# battery_charger.net
KiCad netlist of a schematic drawn in Altium Designer
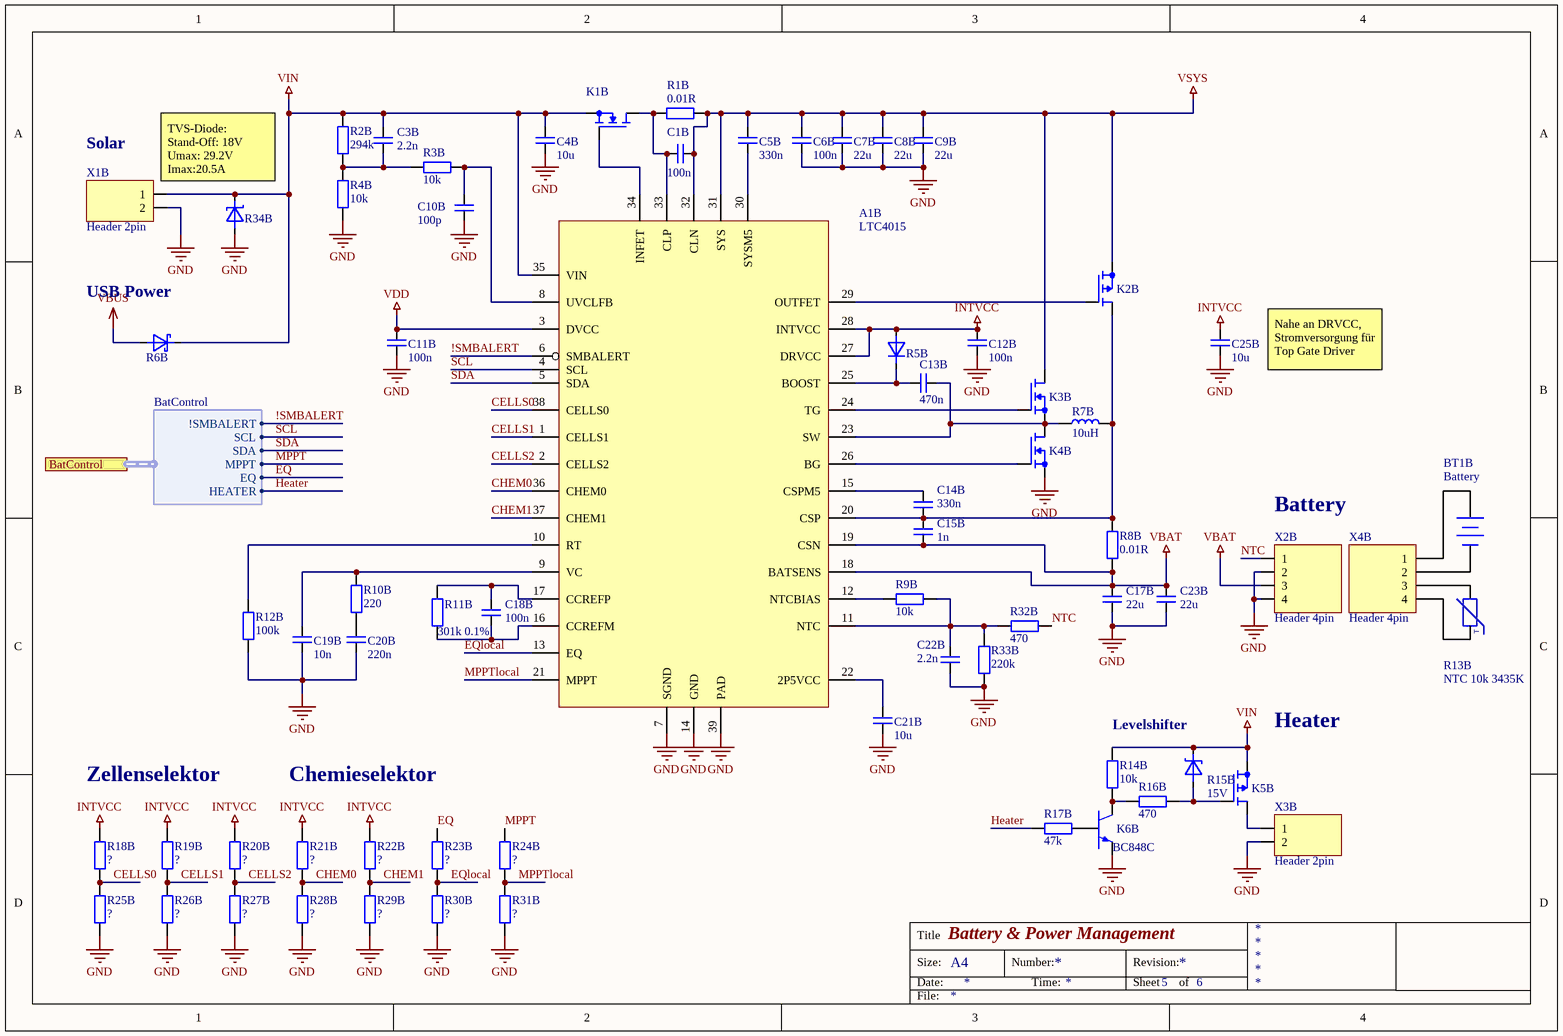
[diagram p0: battery_charger.SchDoc]

(export (version "E")
  (design (tool "Eeschema 10.0.6"))
  (components
    (comp (ref "A1B")
      (value "LTC4015")
      (footprint "QFN38")
      (description "Multichemistry Buck Battery Charger Controller with Digital Telemetry System")
      (libsource (lib "IC") (part "LTC4015"))
    )
    (comp (ref "BT1B")
      (value "Battery")
      (description "Multicell Battery")
      (fields (field (name "PUBLISHER") "Altium Limited"))
      (libsource (lib "Miscellaneous Devices") (part "Battery"))
    )
    (comp (ref "C1B") (value "100n") (footprint "0805") (libsource (lib "Passive") (part "Kondensator")))
    (comp (ref "C3B") (value "2.2n") (footprint "0805") (libsource (lib "Passive") (part "Kondensator")))
    (comp (ref "C4B") (value "10u") (footprint "1812") (libsource (lib "Passive") (part "Kondensator")))
    (comp (ref "C5B") (value "330n") (footprint "0805") (libsource (lib "Passive") (part "Kondensator")))
    (comp (ref "C6B") (value "100n") (footprint "0805") (libsource (lib "Passive") (part "Kondensator")))
    (comp (ref "C7B") (value "22u") (footprint "1812") (libsource (lib "Passive") (part "Kondensator")))
    (comp (ref "C8B") (value "22u") (footprint "1812") (libsource (lib "Passive") (part "Kondensator")))
    (comp (ref "C9B") (value "22u") (footprint "1812") (libsource (lib "Passive") (part "Kondensator")))
    (comp (ref "C10B") (value "100p") (footprint "0805") (libsource (lib "Passive") (part "Kondensator")))
    (comp (ref "C11B") (value "100n") (footprint "0805") (libsource (lib "Passive") (part "Kondensator")))
    (comp (ref "C12B") (value "100n") (footprint "0805") (libsource (lib "Passive") (part "Kondensator")))
    (comp (ref "C13B") (value "470n") (footprint "0805") (libsource (lib "Passive") (part "Kondensator")))
    (comp (ref "C14B") (value "330n") (footprint "0805") (libsource (lib "Passive") (part "Kondensator")))
    (comp (ref "C15B") (value "1n") (footprint "0805") (libsource (lib "Passive") (part "Kondensator")))
    (comp (ref "C17B") (value "22u") (footprint "1210") (libsource (lib "Passive") (part "Kondensator")))
    (comp (ref "C18B") (value "100n") (footprint "0805") (libsource (lib "Passive") (part "Kondensator")))
    (comp (ref "C19B") (value "10n") (footprint "0805") (libsource (lib "Passive") (part "Kondensator")))
    (comp (ref "C20B") (value "220n") (footprint "0805") (libsource (lib "Passive") (part "Kondensator")))
    (comp (ref "C21B") (value "10u") (footprint "0805") (libsource (lib "Passive") (part "Kondensator")))
    (comp (ref "C22B") (value "2.2n") (footprint "0805") (libsource (lib "Passive") (part "Kondensator")))
    (comp (ref "C23B") (value "22u") (footprint "1210") (libsource (lib "Passive") (part "Kondensator")))
    (comp (ref "C25B") (value "10u") (footprint "0805") (libsource (lib "Passive") (part "Kondensator")))
    (comp (ref "K1B")
      (value "FDMC8327L")
      (footprint "Power33")
      (libsource (lib "Discrete_Semiconductors") (part "MOSFET N-channel enh"))
    )
    (comp (ref "K2B")
      (value "SI7611DN")
      (footprint "Power33")
      (libsource (lib "Discrete_Semiconductors") (part "MOSFET P-channel enh"))
    )
    (comp (ref "K3B")
      (value "FDMC8327L")
      (footprint "Power33")
      (libsource (lib "Discrete_Semiconductors") (part "MOSFET N-channel enh"))
    )
    (comp (ref "K4B")
      (value "FDMC8327L")
      (footprint "Power33")
      (libsource (lib "Discrete_Semiconductors") (part "MOSFET N-channel enh"))
    )
    (comp (ref "K5B")
      (value "pmos FDC658")
      (footprint "SuperSOT-6")
      (libsource (lib "Discrete_Semiconductors") (part "MOSFET P-channel enh"))
    )
    (comp (ref "K6B")
      (value "BC848C")
      (footprint "SOT23-3")
      (libsource (lib "Discrete_Semiconductors") (part "Transistor NPN"))
    )
    (comp (ref "R1B") (value "0.01R") (footprint "2512") (libsource (lib "Passive") (part "Widerstand")))
    (comp (ref "R2B") (value "294k") (footprint "0805") (libsource (lib "Passive") (part "Widerstand")))
    (comp (ref "R3B") (value "10k") (footprint "0805") (libsource (lib "Passive") (part "Widerstand")))
    (comp (ref "R4B") (value "10k") (footprint "0805") (libsource (lib "Passive") (part "Widerstand")))
    (comp (ref "R5B")
      (value "1N4148W")
      (footprint "SOD123F")
      (libsource (lib "Discrete_Semiconductors") (part "Diode"))
    )
    (comp (ref "R6B")
      (value "Diode shottky")
      (footprint "PowerDI123")
      (libsource (lib "Discrete_Semiconductors") (part "Diode shottky"))
    )
    (comp (ref "R7B")
      (value "10uH")
      (footprint "INDP_13.2_12.9X3.5M")
      (libsource (lib "Passive") (part "Induktivität"))
    )
    (comp (ref "R8B") (value "0.01R") (footprint "2512") (libsource (lib "Passive") (part "Widerstand")))
    (comp (ref "R9B") (value "10k") (footprint "0805") (libsource (lib "Passive") (part "Widerstand")))
    (comp (ref "R10B") (value "220") (footprint "0805") (libsource (lib "Passive") (part "Widerstand")))
    (comp (ref "R11B") (value "301k 0.1%") (footprint "0805") (libsource (lib "Passive") (part "Widerstand")))
    (comp (ref "R12B") (value "100k") (footprint "0805") (libsource (lib "Passive") (part "Widerstand")))
    (comp (ref "R13B") (value "NTC 10k 3435K") (libsource (lib "Passive") (part "PTC")))
    (comp (ref "R14B") (value "10k") (footprint "0805") (libsource (lib "Passive") (part "Widerstand")))
    (comp (ref "R15B")
      (value "15V")
      (footprint "SOD523")
      (libsource (lib "Discrete_Semiconductors") (part "Diode zener"))
    )
    (comp (ref "R16B") (value "470") (footprint "0805") (libsource (lib "Passive") (part "Widerstand")))
    (comp (ref "R17B") (value "47k") (footprint "0805") (libsource (lib "Passive") (part "Widerstand")))
    (comp (ref "R18B") (value "?") (footprint "0805") (libsource (lib "Passive") (part "Widerstand")))
    (comp (ref "R19B") (value "?") (footprint "0805") (libsource (lib "Passive") (part "Widerstand")))
    (comp (ref "R20B") (value "?") (footprint "0805") (libsource (lib "Passive") (part "Widerstand")))
    (comp (ref "R21B") (value "?") (footprint "0805") (libsource (lib "Passive") (part "Widerstand")))
    (comp (ref "R22B") (value "?") (footprint "0805") (libsource (lib "Passive") (part "Widerstand")))
    (comp (ref "R23B") (value "?") (footprint "0805") (libsource (lib "Passive") (part "Widerstand")))
    (comp (ref "R24B") (value "?") (footprint "0805") (libsource (lib "Passive") (part "Widerstand")))
    (comp (ref "R25B") (value "?") (footprint "0805") (libsource (lib "Passive") (part "Widerstand")))
    (comp (ref "R26B") (value "?") (footprint "0805") (libsource (lib "Passive") (part "Widerstand")))
    (comp (ref "R27B") (value "?") (footprint "0805") (libsource (lib "Passive") (part "Widerstand")))
    (comp (ref "R28B") (value "?") (footprint "0805") (libsource (lib "Passive") (part "Widerstand")))
    (comp (ref "R29B") (value "?") (footprint "0805") (libsource (lib "Passive") (part "Widerstand")))
    (comp (ref "R30B") (value "?") (footprint "0805") (libsource (lib "Passive") (part "Widerstand")))
    (comp (ref "R31B") (value "?") (footprint "0805") (libsource (lib "Passive") (part "Widerstand")))
    (comp (ref "R32B") (value "470") (footprint "0805") (libsource (lib "Passive") (part "Widerstand")))
    (comp (ref "R33B") (value "220k") (footprint "0805") (libsource (lib "Passive") (part "Widerstand")))
    (comp (ref "R34B")
      (value "TVS 29.2Vmax")
      (footprint "DO 214AA")
      (description "unipolar transient voltage suppression diode")
      (libsource (lib "Discrete_Semiconductors") (part "Diode TVS unipolar"))
    )
    (comp (ref "X1B")
      (value "Header 2pin")
      (footprint "PHOENIX_1729128")
      (libsource (lib "Connectors") (part "Header 2pin"))
    )
    (comp (ref "X2B")
      (value "Header 4pin")
      (footprint "Phoenix, 5mm pitch, 4pin")
      (libsource (lib "Connectors") (part "Header 4pin"))
    )
    (comp (ref "X3B")
      (value "Header 2pin")
      (footprint "PHOENIX_1729128")
      (libsource (lib "") (part "Header 2pin_1"))
    )
    (comp (ref "X4B") (value "Header 4pin") (libsource (lib "") (part "Header 4pin_1")))
  )
  (nets
    (net (code "2") (name "/!SMBALERT") (class "Default")
      (node (ref "A1B") (pin "6") (pinfunction "SMBALERT_6") (pintype "passive"))
    )
    (net (code "3") (name "/CELLS0") (class "Default")
      (node (ref "A1B") (pin "38") (pinfunction "CELLS0_38") (pintype "passive"))
      (node (ref "R18B") (pin "2") (pinfunction "2_2") (pintype "passive"))
      (node (ref "R25B") (pin "1") (pinfunction "1_1") (pintype "passive"))
    )
    (net (code "4") (name "/CELLS1") (class "Default")
      (node (ref "A1B") (pin "1") (pinfunction "CELLS1_1") (pintype "passive"))
      (node (ref "R19B") (pin "2") (pinfunction "2_2") (pintype "passive"))
      (node (ref "R26B") (pin "1") (pinfunction "1_1") (pintype "passive"))
    )
    (net (code "5") (name "/CELLS2") (class "Default")
      (node (ref "A1B") (pin "2") (pinfunction "CELLS2_2") (pintype "passive"))
      (node (ref "R20B") (pin "2") (pinfunction "2_2") (pintype "passive"))
      (node (ref "R27B") (pin "1") (pinfunction "1_1") (pintype "passive"))
    )
    (net (code "6") (name "/CHEM0") (class "Default")
      (node (ref "A1B") (pin "36") (pinfunction "CHEM0_36") (pintype "passive"))
      (node (ref "R21B") (pin "2") (pinfunction "2_2") (pintype "passive"))
      (node (ref "R28B") (pin "1") (pinfunction "1_1") (pintype "passive"))
    )
    (net (code "7") (name "/CHEM1") (class "Default")
      (node (ref "A1B") (pin "37") (pinfunction "CHEM1_37") (pintype "passive"))
      (node (ref "R22B") (pin "2") (pinfunction "2_2") (pintype "passive"))
      (node (ref "R29B") (pin "1") (pinfunction "1_1") (pintype "passive"))
    )
    (net (code "8") (name "/EQ") (class "Default")
      (node (ref "R23B") (pin "1") (pinfunction "1_1") (pintype "passive"))
    )
    (net (code "9") (name "/EQlocal") (class "Default")
      (node (ref "A1B") (pin "13") (pinfunction "EQ_13") (pintype "passive"))
      (node (ref "R23B") (pin "2") (pinfunction "2_2") (pintype "passive"))
      (node (ref "R30B") (pin "1") (pinfunction "1_1") (pintype "passive"))
    )
    (net (code "10") (name "/Heater") (class "Default")
      (node (ref "R17B") (pin "1") (pinfunction "1_1") (pintype "passive"))
    )
    (net (code "11") (name "/MPPT") (class "Default")
      (node (ref "R24B") (pin "1") (pinfunction "1_1") (pintype "passive"))
    )
    (net (code "12") (name "/MPPTlocal") (class "Default")
      (node (ref "A1B") (pin "21") (pinfunction "MPPT_21") (pintype "passive"))
      (node (ref "R24B") (pin "2") (pinfunction "2_2") (pintype "passive"))
      (node (ref "R31B") (pin "1") (pinfunction "1_1") (pintype "passive"))
    )
    (net (code "13") (name "/NTC") (class "Default")
      (node (ref "R32B") (pin "2") (pinfunction "2_2") (pintype "passive"))
      (node (ref "X2B") (pin "1") (pinfunction "1_1") (pintype "passive"))
    )
    (net (code "14") (name "/SCL") (class "Default")
      (node (ref "A1B") (pin "4") (pinfunction "SCL_4") (pintype "passive"))
    )
    (net (code "15") (name "/SDA") (class "Default")
      (node (ref "A1B") (pin "5") (pinfunction "SDA_5") (pintype "passive"))
    )
    (net (code "17") (name "GND") (class "Default")
      (node (ref "A1B") (pin "14") (pinfunction "GND_14") (pintype "passive"))
      (node (ref "A1B") (pin "39") (pinfunction "PAD_39") (pintype "passive"))
      (node (ref "A1B") (pin "7") (pinfunction "SGND_7") (pintype "passive"))
      (node (ref "C10B") (pin "1") (pinfunction "1_1") (pintype "passive"))
      (node (ref "C11B") (pin "2") (pinfunction "2_2") (pintype "passive"))
      (node (ref "C12B") (pin "2") (pinfunction "2_2") (pintype "passive"))
      (node (ref "C17B") (pin "2") (pinfunction "2_2") (pintype "passive"))
      (node (ref "C19B") (pin "2") (pinfunction "2_2") (pintype "passive"))
      (node (ref "C20B") (pin "1") (pinfunction "1_1") (pintype "passive"))
      (node (ref "C21B") (pin "2") (pinfunction "2_2") (pintype "passive"))
      (node (ref "C22B") (pin "1") (pinfunction "1_1") (pintype "passive"))
      (node (ref "C23B") (pin "2") (pinfunction "2_2") (pintype "passive"))
      (node (ref "C25B") (pin "2") (pinfunction "2_2") (pintype "passive"))
      (node (ref "C4B") (pin "2") (pinfunction "2_2") (pintype "passive"))
      (node (ref "C6B") (pin "2") (pinfunction "2_2") (pintype "passive"))
      (node (ref "C7B") (pin "2") (pinfunction "2_2") (pintype "passive"))
      (node (ref "C8B") (pin "2") (pinfunction "2_2") (pintype "passive"))
      (node (ref "C9B") (pin "2") (pinfunction "2_2") (pintype "passive"))
      (node (ref "K4B") (pin "2") (pinfunction "Source_2") (pintype "passive"))
      (node (ref "K6B") (pin "2") (pinfunction "Emitter_2") (pintype "passive"))
      (node (ref "R12B") (pin "2") (pinfunction "2_2") (pintype "passive"))
      (node (ref "R25B") (pin "2") (pinfunction "2_2") (pintype "passive"))
      (node (ref "R26B") (pin "2") (pinfunction "2_2") (pintype "passive"))
      (node (ref "R27B") (pin "2") (pinfunction "2_2") (pintype "passive"))
      (node (ref "R28B") (pin "2") (pinfunction "2_2") (pintype "passive"))
      (node (ref "R29B") (pin "2") (pinfunction "2_2") (pintype "passive"))
      (node (ref "R30B") (pin "2") (pinfunction "2_2") (pintype "passive"))
      (node (ref "R31B") (pin "2") (pinfunction "2_2") (pintype "passive"))
      (node (ref "R33B") (pin "2") (pinfunction "2_2") (pintype "passive"))
      (node (ref "R34B") (pin "2") (pinfunction "Annode_2") (pintype "passive"))
      (node (ref "R4B") (pin "1") (pinfunction "1_1") (pintype "passive"))
      (node (ref "X1B") (pin "2") (pinfunction "2_2") (pintype "passive"))
      (node (ref "X2B") (pin "2") (pinfunction "2_2") (pintype "passive"))
      (node (ref "X2B") (pin "4") (pinfunction "4_4") (pintype "passive"))
      (node (ref "X3B") (pin "2") (pinfunction "2_2") (pintype "passive"))
    )
    (net (code "18") (name "INTVCC") (class "Default")
      (node (ref "A1B") (pin "27") (pinfunction "DRVCC_27") (pintype "passive"))
      (node (ref "A1B") (pin "28") (pinfunction "INTVCC_28") (pintype "passive"))
      (node (ref "C12B") (pin "1") (pinfunction "1_1") (pintype "passive"))
      (node (ref "C25B") (pin "1") (pinfunction "1_1") (pintype "passive"))
      (node (ref "R18B") (pin "1") (pinfunction "1_1") (pintype "passive"))
      (node (ref "R19B") (pin "1") (pinfunction "1_1") (pintype "passive"))
      (node (ref "R20B") (pin "1") (pinfunction "1_1") (pintype "passive"))
      (node (ref "R21B") (pin "1") (pinfunction "1_1") (pintype "passive"))
      (node (ref "R22B") (pin "1") (pinfunction "1_1") (pintype "passive"))
      (node (ref "R5B") (pin "2") (pinfunction "Annode_2") (pintype "passive"))
    )
    (net (code "19") (name "Net-(A1B-2P5VCC)") (class "Default")
      (node (ref "A1B") (pin "22") (pinfunction "2P5VCC_22") (pintype "passive"))
      (node (ref "C21B") (pin "1") (pinfunction "1_1") (pintype "passive"))
    )
    (net (code "20") (name "Net-(A1B-BG)") (class "Default")
      (node (ref "A1B") (pin "26") (pinfunction "BG_26") (pintype "passive"))
      (node (ref "K4B") (pin "3") (pinfunction "Gate_3") (pintype "passive"))
    )
    (net (code "21") (name "Net-(A1B-BOOST)") (class "Default")
      (node (ref "A1B") (pin "25") (pinfunction "BOOST_25") (pintype "passive"))
      (node (ref "C13B") (pin "2") (pinfunction "2_2") (pintype "passive"))
      (node (ref "R5B") (pin "1") (pinfunction "Kathode_1") (pintype "passive"))
    )
    (net (code "22") (name "Net-(A1B-CCREFM)") (class "Default")
      (node (ref "A1B") (pin "16") (pinfunction "CCREFM_16") (pintype "passive"))
      (node (ref "C18B") (pin "1") (pinfunction "1_1") (pintype "passive"))
      (node (ref "R11B") (pin "2") (pinfunction "2_2") (pintype "passive"))
    )
    (net (code "23") (name "Net-(A1B-CCREFP)") (class "Default")
      (node (ref "A1B") (pin "17") (pinfunction "CCREFP_17") (pintype "passive"))
      (node (ref "C18B") (pin "2") (pinfunction "2_2") (pintype "passive"))
      (node (ref "R11B") (pin "1") (pinfunction "1_1") (pintype "passive"))
    )
    (net (code "24") (name "Net-(A1B-CLP)") (class "Default")
      (node (ref "A1B") (pin "33") (pinfunction "CLP_33") (pintype "passive"))
      (node (ref "C1B") (pin "2") (pinfunction "2_2") (pintype "passive"))
      (node (ref "K1B") (pin "1") (pinfunction "Drain_1") (pintype "passive"))
      (node (ref "R1B") (pin "2") (pinfunction "2_2") (pintype "passive"))
    )
    (net (code "25") (name "Net-(A1B-CSP)") (class "Default")
      (node (ref "A1B") (pin "20") (pinfunction "CSP_20") (pintype "passive"))
      (node (ref "C14B") (pin "2") (pinfunction "2_2") (pintype "passive"))
      (node (ref "C15B") (pin "2") (pinfunction "2_2") (pintype "passive"))
      (node (ref "K2B") (pin "1") (pinfunction "Drain_1") (pintype "passive"))
      (node (ref "R7B") (pin "2") (pinfunction "2_2") (pintype "passive"))
      (node (ref "R8B") (pin "1") (pinfunction "1_1") (pintype "passive"))
    )
    (net (code "26") (name "Net-(A1B-CSPM5)") (class "Default")
      (node (ref "A1B") (pin "15") (pinfunction "CSPM5_15") (pintype "passive"))
      (node (ref "C14B") (pin "1") (pinfunction "1_1") (pintype "passive"))
    )
    (net (code "27") (name "Net-(A1B-INFET)") (class "Default")
      (node (ref "A1B") (pin "34") (pinfunction "INFET_34") (pintype "passive"))
      (node (ref "K1B") (pin "3") (pinfunction "Gate_3") (pintype "passive"))
    )
    (net (code "28") (name "Net-(A1B-NTC)") (class "Default")
      (node (ref "A1B") (pin "11") (pinfunction "NTC_11") (pintype "passive"))
      (node (ref "C22B") (pin "2") (pinfunction "2_2") (pintype "passive"))
      (node (ref "R32B") (pin "1") (pinfunction "1_1") (pintype "passive"))
      (node (ref "R33B") (pin "1") (pinfunction "1_1") (pintype "passive"))
      (node (ref "R9B") (pin "1") (pinfunction "1_1") (pintype "passive"))
    )
    (net (code "29") (name "Net-(A1B-NTCBIAS)") (class "Default")
      (node (ref "A1B") (pin "12") (pinfunction "NTCBIAS_12") (pintype "passive"))
      (node (ref "R9B") (pin "2") (pinfunction "2_2") (pintype "passive"))
    )
    (net (code "30") (name "Net-(A1B-OUTFET)") (class "Default")
      (node (ref "A1B") (pin "29") (pinfunction "OUTFET_29") (pintype "passive"))
      (node (ref "K2B") (pin "3") (pinfunction "Gate_3") (pintype "passive"))
    )
    (net (code "31") (name "Net-(A1B-RT)") (class "Default")
      (node (ref "A1B") (pin "10") (pinfunction "RT_10") (pintype "passive"))
      (node (ref "R12B") (pin "1") (pinfunction "1_1") (pintype "passive"))
    )
    (net (code "32") (name "Net-(A1B-SW)") (class "Default")
      (node (ref "A1B") (pin "23") (pinfunction "SW_23") (pintype "passive"))
      (node (ref "C13B") (pin "1") (pinfunction "1_1") (pintype "passive"))
      (node (ref "K3B") (pin "2") (pinfunction "Source_2") (pintype "passive"))
      (node (ref "K4B") (pin "1") (pinfunction "Drain_1") (pintype "passive"))
      (node (ref "R7B") (pin "1") (pinfunction "1_1") (pintype "passive"))
    )
    (net (code "33") (name "Net-(A1B-SYSM5)") (class "Default")
      (node (ref "A1B") (pin "30") (pinfunction "SYSM5_30") (pintype "passive"))
      (node (ref "C5B") (pin "2") (pinfunction "2_2") (pintype "passive"))
    )
    (net (code "34") (name "Net-(A1B-TG)") (class "Default")
      (node (ref "A1B") (pin "24") (pinfunction "TG_24") (pintype "passive"))
      (node (ref "K3B") (pin "3") (pinfunction "Gate_3") (pintype "passive"))
    )
    (net (code "35") (name "Net-(A1B-UVCLFB)") (class "Default")
      (node (ref "A1B") (pin "8") (pinfunction "UVCLFB_8") (pintype "passive"))
      (node (ref "C10B") (pin "2") (pinfunction "2_2") (pintype "passive"))
      (node (ref "R3B") (pin "1") (pinfunction "1_1") (pintype "passive"))
    )
    (net (code "36") (name "Net-(A1B-VC)") (class "Default")
      (node (ref "A1B") (pin "9") (pinfunction "VC_9") (pintype "passive"))
      (node (ref "C19B") (pin "1") (pinfunction "1_1") (pintype "passive"))
      (node (ref "R10B") (pin "1") (pinfunction "1_1") (pintype "passive"))
    )
    (net (code "37") (name "Net-(C3B-Pad1)") (class "Default")
      (node (ref "C3B") (pin "1") (pinfunction "1_1") (pintype "passive"))
      (node (ref "R2B") (pin "1") (pinfunction "1_1") (pintype "passive"))
      (node (ref "R3B") (pin "2") (pinfunction "2_2") (pintype "passive"))
      (node (ref "R4B") (pin "2") (pinfunction "2_2") (pintype "passive"))
    )
    (net (code "38") (name "Net-(C20B-Pad2)") (class "Default")
      (node (ref "C20B") (pin "2") (pinfunction "2_2") (pintype "passive"))
      (node (ref "R10B") (pin "2") (pinfunction "2_2") (pintype "passive"))
    )
    (net (code "39") (name "Net-(K5B-Drain)") (class "Default")
      (node (ref "K5B") (pin "1") (pinfunction "Drain_1") (pintype "passive"))
      (node (ref "X3B") (pin "1") (pinfunction "1_1") (pintype "passive"))
    )
    (net (code "40") (name "Net-(K5B-Gate)") (class "Default")
      (node (ref "K5B") (pin "3") (pinfunction "Gate_3") (pintype "passive"))
      (node (ref "R15B") (pin "2") (pinfunction "Annode_2") (pintype "passive"))
      (node (ref "R16B") (pin "2") (pinfunction "2_2") (pintype "passive"))
    )
    (net (code "41") (name "Net-(K6B-Basis)") (class "Default")
      (node (ref "K6B") (pin "3") (pinfunction "Basis_3") (pintype "passive"))
      (node (ref "R17B") (pin "2") (pinfunction "2_2") (pintype "passive"))
    )
    (net (code "42") (name "Net-(K6B-Collector)") (class "Default")
      (node (ref "K6B") (pin "1") (pinfunction "Collector_1") (pintype "passive"))
      (node (ref "R14B") (pin "1") (pinfunction "1_1") (pintype "passive"))
      (node (ref "R16B") (pin "1") (pinfunction "1_1") (pintype "passive"))
    )
    (net (code "43") (name "VBAT") (class "Default")
      (node (ref "A1B") (pin "18") (pinfunction "BATSENS_18") (pintype "passive"))
      (node (ref "A1B") (pin "19") (pinfunction "CSN_19") (pintype "passive"))
      (node (ref "C15B") (pin "1") (pinfunction "1_1") (pintype "passive"))
      (node (ref "C17B") (pin "1") (pinfunction "1_1") (pintype "passive"))
      (node (ref "C23B") (pin "1") (pinfunction "1_1") (pintype "passive"))
      (node (ref "R8B") (pin "2") (pinfunction "2_2") (pintype "passive"))
      (node (ref "X2B") (pin "3") (pinfunction "3_3") (pintype "passive"))
    )
    (net (code "44") (name "VBUS") (class "Default")
      (node (ref "R6B") (pin "2") (pinfunction "Annode_2") (pintype "passive"))
    )
    (net (code "45") (name "VDD") (class "Default")
      (node (ref "A1B") (pin "3") (pinfunction "DVCC_3") (pintype "passive"))
      (node (ref "C11B") (pin "1") (pinfunction "1_1") (pintype "passive"))
    )
    (net (code "46") (name "VIN") (class "Default")
      (node (ref "A1B") (pin "35") (pinfunction "VIN_35") (pintype "passive"))
      (node (ref "C3B") (pin "2") (pinfunction "2_2") (pintype "passive"))
      (node (ref "C4B") (pin "1") (pinfunction "1_1") (pintype "passive"))
      (node (ref "K1B") (pin "2") (pinfunction "Source_2") (pintype "passive"))
      (node (ref "K5B") (pin "2") (pinfunction "Source_2") (pintype "passive"))
      (node (ref "R14B") (pin "2") (pinfunction "2_2") (pintype "passive"))
      (node (ref "R15B") (pin "1") (pinfunction "Kathode_1") (pintype "passive"))
      (node (ref "R2B") (pin "2") (pinfunction "2_2") (pintype "passive"))
      (node (ref "R34B") (pin "1") (pinfunction "Kathode_1") (pintype "passive"))
      (node (ref "R6B") (pin "1") (pinfunction "Kathode_1") (pintype "passive"))
      (node (ref "X1B") (pin "1") (pinfunction "1_1") (pintype "passive"))
    )
    (net (code "47") (name "VSYS") (class "Default")
      (node (ref "A1B") (pin "31") (pinfunction "SYS_31") (pintype "passive"))
      (node (ref "A1B") (pin "32") (pinfunction "CLN_32") (pintype "passive"))
      (node (ref "C1B") (pin "1") (pinfunction "1_1") (pintype "passive"))
      (node (ref "C5B") (pin "1") (pinfunction "1_1") (pintype "passive"))
      (node (ref "C6B") (pin "1") (pinfunction "1_1") (pintype "passive"))
      (node (ref "C7B") (pin "1") (pinfunction "1_1") (pintype "passive"))
      (node (ref "C8B") (pin "1") (pinfunction "1_1") (pintype "passive"))
      (node (ref "C9B") (pin "1") (pinfunction "1_1") (pintype "passive"))
      (node (ref "K2B") (pin "2") (pinfunction "Source_2") (pintype "passive"))
      (node (ref "K3B") (pin "1") (pinfunction "Drain_1") (pintype "passive"))
      (node (ref "R1B") (pin "1") (pinfunction "1_1") (pintype "passive"))
    )
    (net (code "48") (name "unconnected-(BT1B-+-Pad1)") (class "Default")
      (node (ref "BT1B") (pin "1") (pinfunction "+_1") (pintype "passive"))
    )
    (net (code "49") (name "unconnected-(BT1B---Pad2)") (class "Default")
      (node (ref "BT1B") (pin "2") (pinfunction "-_2") (pintype "passive"))
    )
    (net (code "50") (name "unconnected-(R13B-Pad1)") (class "Default")
      (node (ref "R13B") (pin "1") (pintype "passive"))
    )
    (net (code "51") (name "unconnected-(R13B-Pad2)") (class "Default")
      (node (ref "R13B") (pin "2") (pintype "passive"))
    )
    (net (code "52") (name "unconnected-(X4B-Pad1)") (class "Default")
      (node (ref "X4B") (pin "1") (pinfunction "1_1") (pintype "passive"))
    )
    (net (code "53") (name "unconnected-(X4B-Pad2)") (class "Default")
      (node (ref "X4B") (pin "2") (pinfunction "2_2") (pintype "passive"))
    )
    (net (code "54") (name "unconnected-(X4B-Pad3)") (class "Default")
      (node (ref "X4B") (pin "3") (pinfunction "3_3") (pintype "passive"))
    )
    (net (code "55") (name "unconnected-(X4B-Pad4)") (class "Default")
      (node (ref "X4B") (pin "4") (pinfunction "4_4") (pintype "passive"))
    )
  )
)
